# sensor.net
KiCad netlist of a schematic drawn in Altium Designer
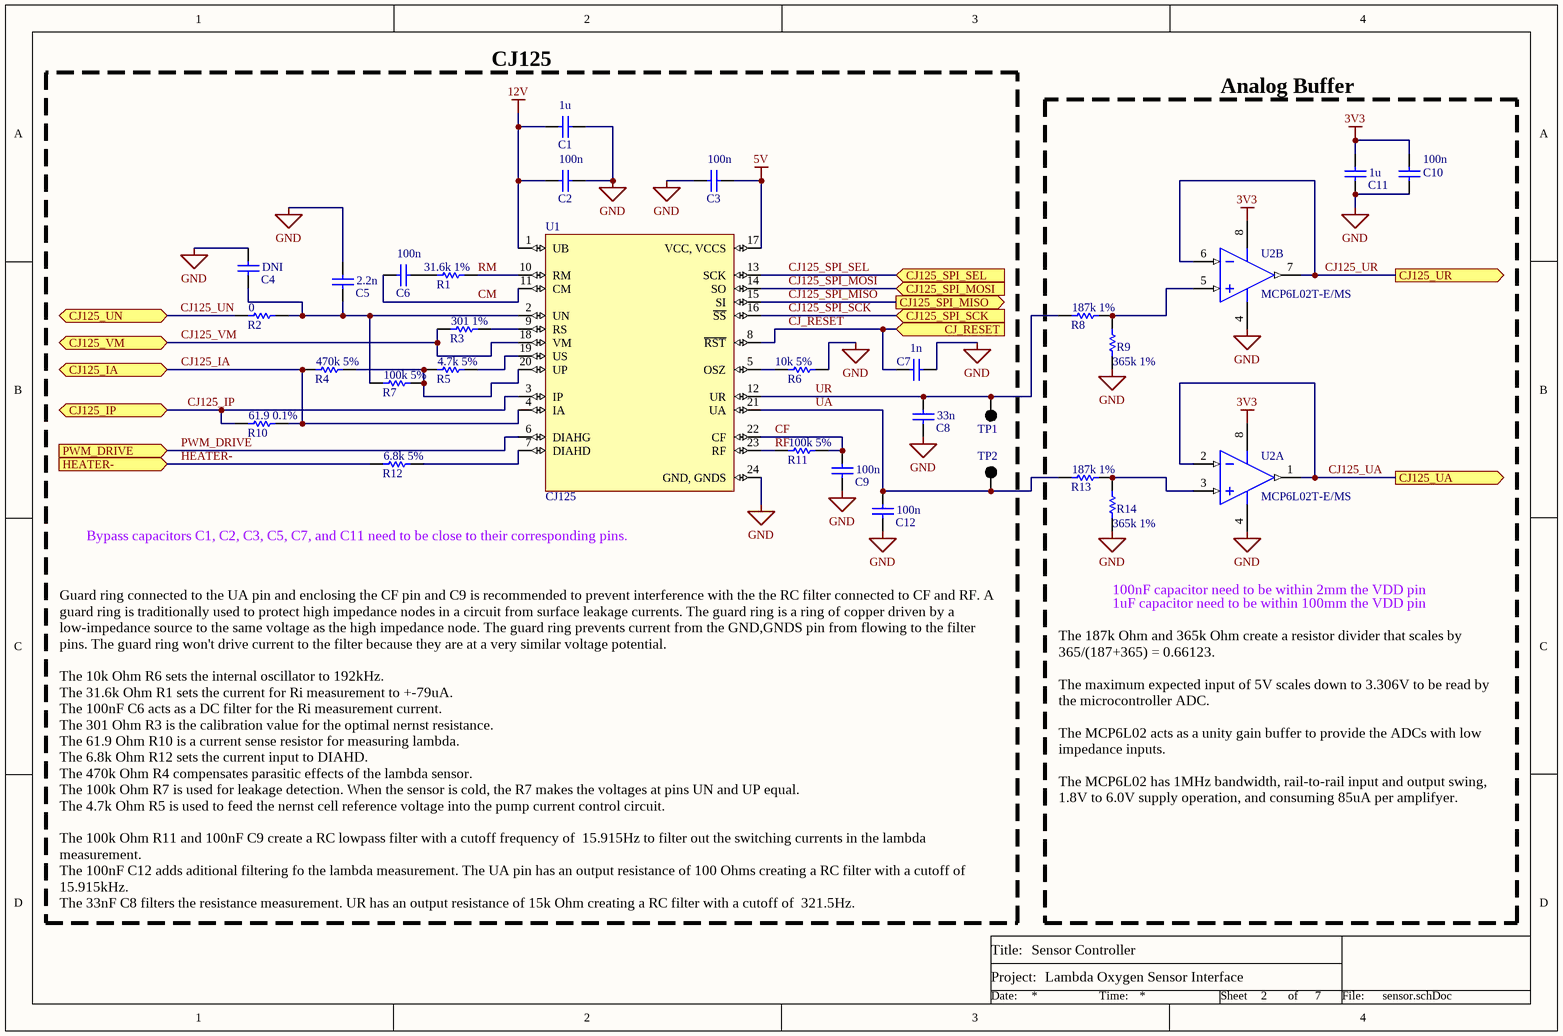
[diagram p0: sensor.schDoc]

(export (version "E")
  (design (tool "Eeschema 10.0.6"))
  (components
    (comp (ref "C1")
      (value "1u")
      (footprint "0805")
      (description "Generic 0805 Capacitor")
      (libsource (lib "symbol_library") (part "C_0805"))
    )
    (comp (ref "C2")
      (value "100n")
      (footprint "0805")
      (description "Generic 0805 Capacitor")
      (libsource (lib "symbol_library") (part "C_0805"))
    )
    (comp (ref "C3")
      (value "100n")
      (footprint "0805")
      (description "Generic 0805 Capacitor")
      (libsource (lib "symbol_library") (part "C_0805"))
    )
    (comp (ref "C4")
      (value "DNI")
      (footprint "0805")
      (description "Generic 0805 Capacitor")
      (libsource (lib "symbol_library") (part "C_0805"))
    )
    (comp (ref "C5")
      (value "2.2n")
      (footprint "0805")
      (description "Generic 0805 Capacitor")
      (libsource (lib "symbol_library") (part "C_0805"))
    )
    (comp (ref "C6")
      (value "100n")
      (footprint "0805")
      (description "Generic 0805 Capacitor")
      (libsource (lib "symbol_library") (part "C_0805"))
    )
    (comp (ref "C7")
      (value "1n")
      (footprint "0805")
      (description "Generic 0805 Capacitor")
      (libsource (lib "symbol_library") (part "C_0805"))
    )
    (comp (ref "C8")
      (value "33n")
      (footprint "0805")
      (description "Generic 0805 Capacitor")
      (libsource (lib "symbol_library") (part "C_0805"))
    )
    (comp (ref "C9")
      (value "100n")
      (footprint "0805")
      (description "Generic 0805 Capacitor")
      (libsource (lib "symbol_library") (part "C_0805"))
    )
    (comp (ref "C10")
      (value "100n")
      (footprint "0805")
      (description "Generic 0805 Capacitor")
      (libsource (lib "symbol_library") (part "C_0805"))
    )
    (comp (ref "C11")
      (value "1u")
      (footprint "1206")
      (description "Generic 1206 Capacitor")
      (libsource (lib "symbol_library") (part "C_1206"))
    )
    (comp (ref "C12")
      (value "100n")
      (footprint "0805")
      (description "Generic 0805 Capacitor")
      (libsource (lib "symbol_library") (part "C_0805"))
    )
    (comp (ref "R1")
      (value "31.6k 1%")
      (footprint "0603")
      (description "Generic 0603 Resistor")
      (libsource (lib "symbol_library") (part "R_0603"))
    )
    (comp (ref "R2")
      (value "0")
      (footprint "0603")
      (description "Generic 0603 Resistor")
      (libsource (lib "symbol_library") (part "R_0603"))
    )
    (comp (ref "R3")
      (value "301 1%")
      (footprint "0603")
      (description "Generic 0603 Resistor")
      (libsource (lib "symbol_library") (part "R_0603"))
    )
    (comp (ref "R4")
      (value "470k 5%")
      (footprint "0603")
      (description "Generic 0603 Resistor")
      (libsource (lib "symbol_library") (part "R_0603"))
    )
    (comp (ref "R5")
      (value "4.7k 5%")
      (footprint "0603")
      (description "Generic 0603 Resistor")
      (libsource (lib "symbol_library") (part "R_0603"))
    )
    (comp (ref "R6")
      (value "10k 5%")
      (footprint "0603")
      (description "Generic 0603 Resistor")
      (libsource (lib "symbol_library") (part "R_0603"))
    )
    (comp (ref "R7")
      (value "100k 5%")
      (footprint "0603")
      (description "Generic 0603 Resistor")
      (libsource (lib "symbol_library") (part "R_0603"))
    )
    (comp (ref "R8")
      (value "187k 1%")
      (footprint "0603")
      (description "Generic 0603 Resistor")
      (libsource (lib "symbol_library") (part "R_0603"))
    )
    (comp (ref "R9")
      (value "365k 1%")
      (footprint "0603")
      (description "Generic 0603 Resistor")
      (libsource (lib "symbol_library") (part "R_0603"))
    )
    (comp (ref "R10")
      (value "61.9 0.1%")
      (footprint "0603")
      (description "Generic 0603 Resistor")
      (libsource (lib "symbol_library") (part "R_0603"))
    )
    (comp (ref "R11")
      (value "100k 5%")
      (footprint "0603")
      (description "Generic 0603 Resistor")
      (libsource (lib "symbol_library") (part "R_0603"))
    )
    (comp (ref "R12")
      (value "6.8k 5%")
      (footprint "0603")
      (description "Generic 0603 Resistor")
      (libsource (lib "symbol_library") (part "R_0603"))
    )
    (comp (ref "R13")
      (value "187k 1%")
      (footprint "0603")
      (description "Generic 0603 Resistor")
      (libsource (lib "symbol_library") (part "R_0603"))
    )
    (comp (ref "R14")
      (value "365k 1%")
      (footprint "0603")
      (description "Generic 0603 Resistor")
      (libsource (lib "symbol_library") (part "R_0603"))
    )
    (comp (ref "TP1")
      (value "5001")
      (footprint "KSTN-5001")
      (description "Test Point, Black, 1-Pin THD, RoHS, Bulk")
      (fields (field (name "MANUFACTURER") "Keystone"))
      (libsource (lib "symbol_library") (part "TP5001"))
    )
    (comp (ref "TP2")
      (value "5001")
      (footprint "KSTN-5001")
      (description "Test Point, Black, 1-Pin THD, RoHS, Bulk")
      (fields (field (name "MANUFACTURER") "Keystone"))
      (libsource (lib "symbol_library") (part "TP5001"))
    )
    (comp (ref "U1")
      (value "CJ125")
      (footprint "SOIC-24")
      (description "5V 2Mbaud SMT Lambda Probe Interface IC - SOIC-24")
      (libsource (lib "symbol_library") (part "CJ125"))
    )
    (comp (ref "U2")
      (value "MCP6L02T-E/MS")
      (footprint "MSOP8_M")
      (description "1 MHz, 85 渭A Dual Op Amp, 8-Pin MSOP, Extended Temperature Range, Tape and Reel")
      (libsource (lib "symbol_library") (part "MCP6L02"))
    )
  )
  (nets
    (net (code "1") (name "/CF") (class "Default")
      (node (ref "C9") (pin "2") (pinfunction "2_2") (pintype "passive"))
      (node (ref "R11") (pin "2") (pinfunction "2_2") (pintype "passive"))
      (node (ref "U1") (pin "22") (pinfunction "CF_22") (pintype "bidirectional"))
    )
    (net (code "2") (name "/CJ125_IA") (class "Default")
      (node (ref "R10") (pin "2") (pinfunction "2_2") (pintype "passive"))
      (node (ref "R4") (pin "1") (pinfunction "1_1") (pintype "passive"))
      (node (ref "U1") (pin "4") (pinfunction "IA_4") (pintype "bidirectional"))
    )
    (net (code "3") (name "/CJ125_IP") (class "Default")
      (node (ref "R10") (pin "1") (pinfunction "1_1") (pintype "passive"))
      (node (ref "U1") (pin "3") (pinfunction "IP_3") (pintype "bidirectional"))
    )
    (net (code "4") (name "/CJ125_SPI_MISO") (class "Default")
      (node (ref "U1") (pin "15") (pinfunction "SI_15") (pintype "bidirectional"))
    )
    (net (code "5") (name "/CJ125_SPI_MOSI") (class "Default")
      (node (ref "U1") (pin "14") (pinfunction "SO_14") (pintype "bidirectional"))
    )
    (net (code "6") (name "/CJ125_SPI_SCK") (class "Default")
      (node (ref "U1") (pin "16") (pinfunction "~{SS}_16") (pintype "bidirectional"))
    )
    (net (code "7") (name "/CJ125_SPI_SEL") (class "Default")
      (node (ref "U1") (pin "13") (pinfunction "SCK_13") (pintype "bidirectional"))
    )
    (net (code "8") (name "/CJ125_UA") (class "Default")
      (node (ref "U2") (pin "1") (pinfunction "VOUTA_1") (pintype "output"))
      (node (ref "U2") (pin "2") (pinfunction "VINA-_2") (pintype "input"))
    )
    (net (code "9") (name "/CJ125_UN") (class "Default")
      (node (ref "R2") (pin "1") (pinfunction "1_1") (pintype "passive"))
    )
    (net (code "10") (name "/CJ125_UR") (class "Default")
      (node (ref "U2") (pin "6") (pinfunction "VINB-_6") (pintype "input"))
      (node (ref "U2") (pin "7") (pinfunction "VOUTB_7") (pintype "output"))
    )
    (net (code "11") (name "/CJ125_VM") (class "Default")
      (node (ref "R3") (pin "1") (pinfunction "1_1") (pintype "passive"))
      (node (ref "U1") (pin "18") (pinfunction "VM_18") (pintype "bidirectional"))
    )
    (net (code "12") (name "/CJ_RESET") (class "Default")
      (node (ref "C7") (pin "1") (pinfunction "1_1") (pintype "passive"))
      (node (ref "U1") (pin "8") (pinfunction "~{RST}_8") (pintype "bidirectional"))
    )
    (net (code "13") (name "/CM") (class "Default")
      (node (ref "C6") (pin "1") (pinfunction "1_1") (pintype "passive"))
      (node (ref "U1") (pin "11") (pinfunction "CM_11") (pintype "bidirectional"))
    )
    (net (code "14") (name "/HEATER-") (class "Default")
      (node (ref "R12") (pin "1") (pinfunction "1_1") (pintype "passive"))
    )
    (net (code "15") (name "/PWM_DRIVE") (class "Default")
      (node (ref "U1") (pin "6") (pinfunction "DIAHG_6") (pintype "bidirectional"))
    )
    (net (code "16") (name "/RF") (class "Default")
      (node (ref "R11") (pin "1") (pinfunction "1_1") (pintype "passive"))
      (node (ref "U1") (pin "23") (pinfunction "RF_23") (pintype "bidirectional"))
    )
    (net (code "17") (name "/RM") (class "Default")
      (node (ref "R1") (pin "2") (pinfunction "2_2") (pintype "passive"))
      (node (ref "U1") (pin "10") (pinfunction "RM_10") (pintype "bidirectional"))
    )
    (net (code "18") (name "/UA") (class "Default")
      (node (ref "C12") (pin "2") (pinfunction "2_2") (pintype "passive"))
      (node (ref "R13") (pin "1") (pinfunction "1_1") (pintype "passive"))
      (node (ref "TP2") (pin "1") (pintype "passive"))
      (node (ref "U1") (pin "21") (pinfunction "UA_21") (pintype "bidirectional"))
    )
    (net (code "19") (name "/UR") (class "Default")
      (node (ref "C8") (pin "2") (pinfunction "2_2") (pintype "passive"))
      (node (ref "R8") (pin "1") (pinfunction "1_1") (pintype "passive"))
      (node (ref "TP1") (pin "1") (pintype "passive"))
      (node (ref "U1") (pin "12") (pinfunction "UR_12") (pintype "bidirectional"))
    )
    (net (code "20") (name "3V3") (class "Default")
      (node (ref "C10") (pin "2") (pinfunction "2_2") (pintype "passive"))
      (node (ref "C11") (pin "2") (pinfunction "2_2") (pintype "passive"))
      (node (ref "U2") (pin "8") (pinfunction "VDD_8") (pintype "power_in"))
    )
    (net (code "21") (name "5V") (class "Default")
      (node (ref "C3") (pin "1") (pinfunction "1_1") (pintype "passive"))
      (node (ref "U1") (pin "17") (pinfunction "VCC,_VCCS_17") (pintype "bidirectional"))
    )
    (net (code "22") (name "12V") (class "Default")
      (node (ref "C1") (pin "1") (pinfunction "1_1") (pintype "passive"))
      (node (ref "C2") (pin "2") (pinfunction "2_2") (pintype "passive"))
      (node (ref "U1") (pin "1") (pinfunction "UB_1") (pintype "bidirectional"))
    )
    (net (code "23") (name "GND") (class "Default")
      (node (ref "C1") (pin "2") (pinfunction "2_2") (pintype "passive"))
      (node (ref "C10") (pin "1") (pinfunction "1_1") (pintype "passive"))
      (node (ref "C11") (pin "1") (pinfunction "1_1") (pintype "passive"))
      (node (ref "C12") (pin "1") (pinfunction "1_1") (pintype "passive"))
      (node (ref "C2") (pin "1") (pinfunction "1_1") (pintype "passive"))
      (node (ref "C3") (pin "2") (pinfunction "2_2") (pintype "passive"))
      (node (ref "C4") (pin "2") (pinfunction "2_2") (pintype "passive"))
      (node (ref "C5") (pin "2") (pinfunction "2_2") (pintype "passive"))
      (node (ref "C7") (pin "2") (pinfunction "2_2") (pintype "passive"))
      (node (ref "C8") (pin "1") (pinfunction "1_1") (pintype "passive"))
      (node (ref "C9") (pin "1") (pinfunction "1_1") (pintype "passive"))
      (node (ref "R14") (pin "1") (pinfunction "1_1") (pintype "passive"))
      (node (ref "R6") (pin "2") (pinfunction "2_2") (pintype "passive"))
      (node (ref "R9") (pin "1") (pinfunction "1_1") (pintype "passive"))
      (node (ref "U1") (pin "24") (pinfunction "GND,_GNDS_24") (pintype "bidirectional"))
      (node (ref "U2") (pin "4") (pinfunction "VSS_4") (pintype "power_in"))
    )
    (net (code "24") (name "Net-(C6-Pad2)") (class "Default")
      (node (ref "C6") (pin "2") (pinfunction "2_2") (pintype "passive"))
      (node (ref "R1") (pin "1") (pinfunction "1_1") (pintype "passive"))
    )
    (net (code "25") (name "Net-(U1-DIAHD)") (class "Default")
      (node (ref "R12") (pin "2") (pinfunction "2_2") (pintype "passive"))
      (node (ref "U1") (pin "7") (pinfunction "DIAHD_7") (pintype "bidirectional"))
    )
    (net (code "26") (name "Net-(U1-OSZ)") (class "Default")
      (node (ref "R6") (pin "1") (pinfunction "1_1") (pintype "passive"))
      (node (ref "U1") (pin "5") (pinfunction "OSZ_5") (pintype "bidirectional"))
    )
    (net (code "27") (name "Net-(U1-RS)") (class "Default")
      (node (ref "R3") (pin "2") (pinfunction "2_2") (pintype "passive"))
      (node (ref "U1") (pin "9") (pinfunction "RS_9") (pintype "bidirectional"))
    )
    (net (code "28") (name "Net-(U1-UN)") (class "Default")
      (node (ref "C4") (pin "1") (pinfunction "1_1") (pintype "passive"))
      (node (ref "C5") (pin "1") (pinfunction "1_1") (pintype "passive"))
      (node (ref "R2") (pin "2") (pinfunction "2_2") (pintype "passive"))
      (node (ref "R7") (pin "1") (pinfunction "1_1") (pintype "passive"))
      (node (ref "U1") (pin "2") (pinfunction "UN_2") (pintype "bidirectional"))
    )
    (net (code "29") (name "Net-(U1-UP)") (class "Default")
      (node (ref "R4") (pin "2") (pinfunction "2_2") (pintype "passive"))
      (node (ref "R5") (pin "1") (pinfunction "1_1") (pintype "passive"))
      (node (ref "R7") (pin "2") (pinfunction "2_2") (pintype "passive"))
      (node (ref "U1") (pin "20") (pinfunction "UP_20") (pintype "bidirectional"))
    )
    (net (code "30") (name "Net-(U1-US)") (class "Default")
      (node (ref "R5") (pin "2") (pinfunction "2_2") (pintype "passive"))
      (node (ref "U1") (pin "19") (pinfunction "US_19") (pintype "bidirectional"))
    )
    (net (code "31") (name "Net-(U2A-VINA+)") (class "Default")
      (node (ref "R13") (pin "2") (pinfunction "2_2") (pintype "passive"))
      (node (ref "R14") (pin "2") (pinfunction "2_2") (pintype "passive"))
      (node (ref "U2") (pin "3") (pinfunction "VINA+_3") (pintype "input"))
    )
    (net (code "32") (name "Net-(U2B-VINB+)") (class "Default")
      (node (ref "R8") (pin "2") (pinfunction "2_2") (pintype "passive"))
      (node (ref "R9") (pin "2") (pinfunction "2_2") (pintype "passive"))
      (node (ref "U2") (pin "5") (pinfunction "VINB+_5") (pintype "input"))
    )
  )
)
